# sensors.net
KiCad netlist of a schematic drawn in Altium Designer
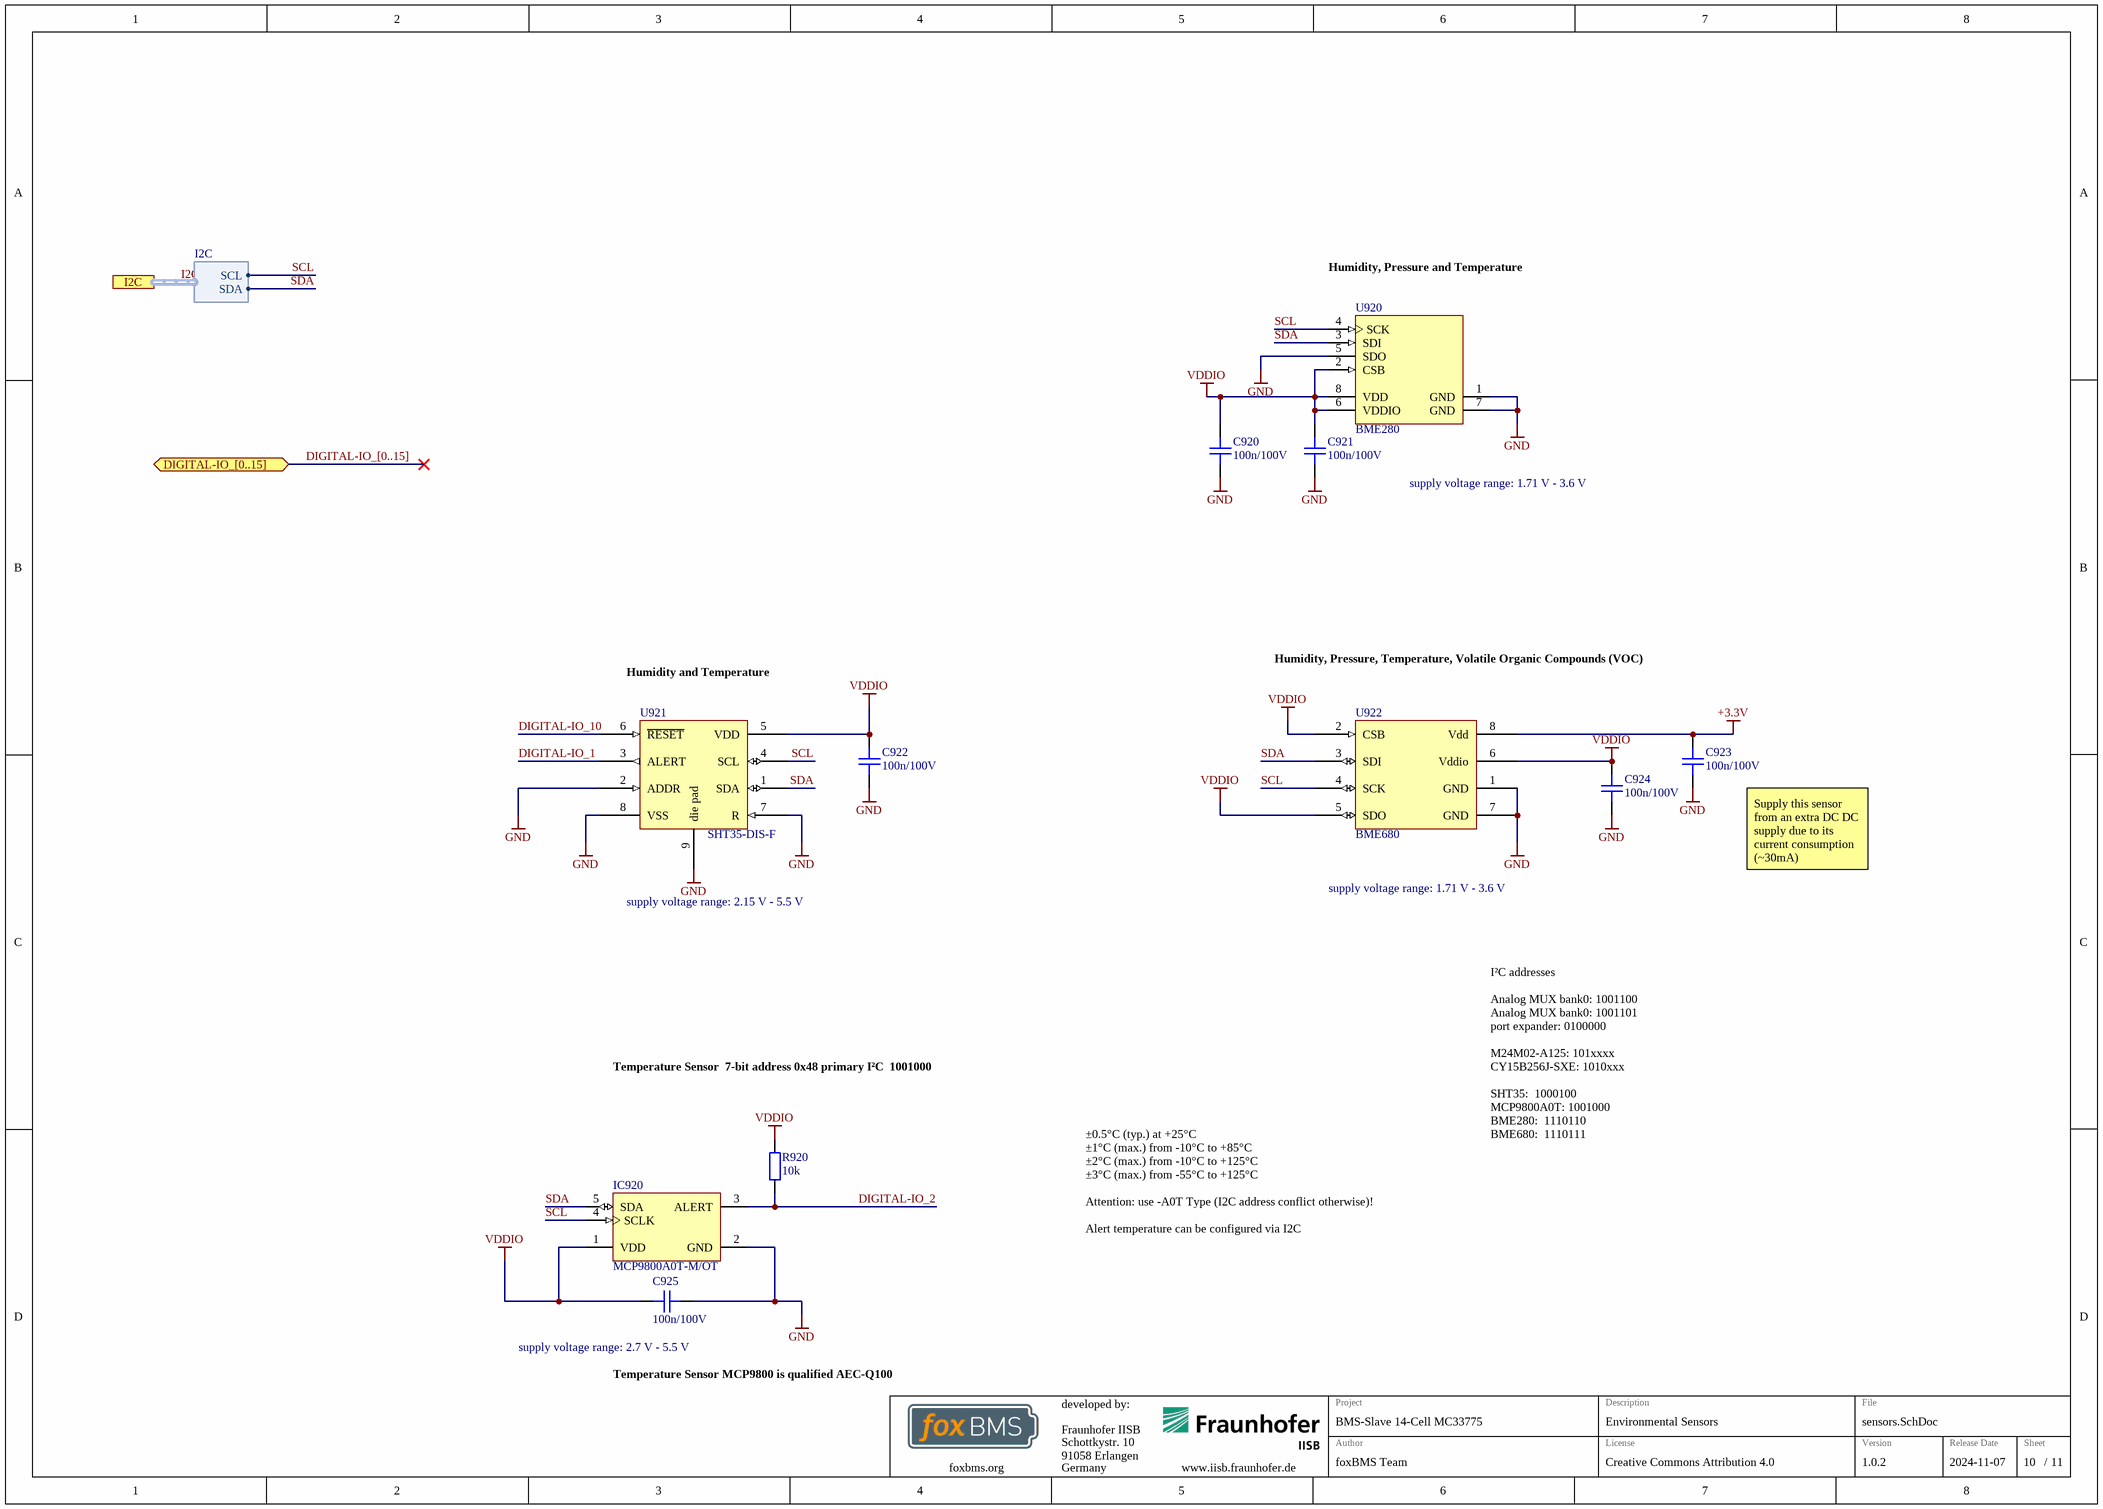
[diagram p0: sensors.SchDoc]

(export (version "E")
  (design (tool "Eeschema 10.0.6"))
  (components
    (comp (ref "C920")
      (value "100n/100V")
      (footprint "CAPC1608X08N")
      (description "MLCC")
      (fields (field (name "PART NUMBER") "gen_C_ceramic_100n_100V_X7R_0603"))
      (libsource (lib "OE750") (part "C"))
    )
    (comp (ref "C921")
      (value "100n/100V")
      (footprint "CAPC1608X08N")
      (description "MLCC")
      (fields (field (name "PART NUMBER") "gen_C_ceramic_100n_100V_X7R_0603"))
      (libsource (lib "OE750") (part "C"))
    )
    (comp (ref "C922")
      (value "100n/100V")
      (footprint "CAPC1608X08N")
      (description "MLCC")
      (fields (field (name "PART NUMBER") "gen_C_ceramic_100n_100V_X7R_0603"))
      (libsource (lib "OE750") (part "C"))
    )
    (comp (ref "C923")
      (value "100n/100V")
      (footprint "CAPC1608X08N")
      (description "MLCC")
      (fields (field (name "PART NUMBER") "gen_C_ceramic_100n_100V_X7R_0603"))
      (libsource (lib "OE750") (part "C"))
    )
    (comp (ref "C924")
      (value "100n/100V")
      (footprint "CAPC1608X08N")
      (description "MLCC")
      (fields (field (name "PART NUMBER") "gen_C_ceramic_100n_100V_X7R_0603"))
      (libsource (lib "OE750") (part "C"))
    )
    (comp (ref "C925")
      (value "100n/100V")
      (footprint "CAPC1608X08N")
      (description "MLCC")
      (fields (field (name "PART NUMBER") "gen_C_ceramic_100n_100V_X7R_0603"))
      (libsource (lib "OE750") (part "C"))
    )
    (comp (ref "IC920")
      (value "MCP9800A0T-M/OT")
      (footprint "SOT-23-OT5_L")
      (libsource (lib "Altium Content Vault") (part "SEN-TEMP-MCP980X-5"))
    )
    (comp (ref "R920")
      (value "10k")
      (footprint "RESC1608X05N")
      (description "SMD Resistor 10k 0603")
      (fields (field (name "PART NUMBER") "gen_R_10k_0603") (field (name "TOLERANCE") "1%"))
      (libsource (lib "OE750") (part "R"))
    )
    (comp (ref "U920")
      (value "BME280")
      (footprint "BOSC-BME280-8_V")
      (description "Low power pressure, temperature & humidity sensor")
      (fields (field (name "MANUFACTURER") "Bosch Sensortec"))
      (libsource (lib "OE750") (part "BME280"))
    )
    (comp (ref "U921")
      (value "SHT35-DIS-F")
      (footprint "SHT3X")
      (description "Humidity/Temp Sensor, Digital, Dfn-8")
      (fields (field (name "MANUFACTURER") "Sensirion"))
      (libsource (lib "OE750") (part "SHT3x-DIS"))
    )
    (comp (ref "U922")
      (value "BME680")
      (footprint "BME680")
      (description "Low power gas, pressure, temperature & humidity sensor")
      (fields (field (name "MANUFACTURER") "Bosch Sensortec"))
      (libsource (lib "OE750") (part "BME680"))
    )
  )
  (nets
    (net (code "15") (name "+3.3V") (class "Default")
      (node (ref "C923") (pin "2") (pinfunction "2_2") (pintype "passive"))
      (node (ref "U922") (pin "8") (pinfunction "Vdd_8") (pintype "power_in"))
    )
    (net (code "16") (name "/DIGITAL-IO_1") (class "Default")
      (node (ref "U921") (pin "3") (pinfunction "ALERT_3") (pintype "output"))
    )
    (net (code "17") (name "/DIGITAL-IO_2") (class "Default")
      (node (ref "IC920") (pin "3") (pinfunction "ALERT_3") (pintype "open_collector"))
      (node (ref "R920") (pin "1") (pinfunction "1_1") (pintype "passive"))
    )
    (net (code "18") (name "/DIGITAL-IO_10") (class "Default")
      (node (ref "U921") (pin "6") (pinfunction "~{RESET}_6") (pintype "input"))
    )
    (net (code "21") (name "/SCL") (class "Default")
      (node (ref "IC920") (pin "4") (pinfunction "SCLK_4") (pintype "input"))
      (node (ref "U920") (pin "4") (pinfunction "SCK_4") (pintype "input"))
      (node (ref "U921") (pin "4") (pinfunction "SCL_4") (pintype "bidirectional"))
      (node (ref "U922") (pin "4") (pinfunction "SCK_4") (pintype "bidirectional"))
    )
    (net (code "22") (name "/SDA") (class "Default")
      (node (ref "IC920") (pin "5") (pinfunction "SDA_5") (pintype "bidirectional"))
      (node (ref "U920") (pin "3") (pinfunction "SDI_3") (pintype "input"))
      (node (ref "U921") (pin "1") (pinfunction "SDA_1") (pintype "bidirectional"))
      (node (ref "U922") (pin "3") (pinfunction "SDI_3") (pintype "bidirectional"))
    )
    (net (code "23") (name "GND") (class "Default")
      (node (ref "C920") (pin "1") (pinfunction "1_1") (pintype "passive"))
      (node (ref "C921") (pin "1") (pinfunction "1_1") (pintype "passive"))
      (node (ref "C922") (pin "1") (pinfunction "1_1") (pintype "passive"))
      (node (ref "C923") (pin "1") (pinfunction "1_1") (pintype "passive"))
      (node (ref "C924") (pin "1") (pinfunction "1_1") (pintype "passive"))
      (node (ref "C925") (pin "1") (pinfunction "1_1") (pintype "passive"))
      (node (ref "IC920") (pin "2") (pinfunction "GND_2") (pintype "power_in"))
      (node (ref "U920") (pin "1") (pinfunction "GND_1") (pintype "power_in"))
      (node (ref "U920") (pin "5") (pinfunction "SDO_5") (pintype "passive"))
      (node (ref "U920") (pin "7") (pinfunction "GND_7") (pintype "power_in"))
      (node (ref "U921") (pin "2") (pinfunction "ADDR_2") (pintype "input"))
      (node (ref "U921") (pin "7") (pinfunction "R_7") (pintype "input"))
      (node (ref "U921") (pin "8") (pinfunction "VSS_8") (pintype "power_in"))
      (node (ref "U921") (pin "9") (pinfunction "die_pad_9") (pintype "power_in"))
      (node (ref "U922") (pin "1") (pinfunction "GND_1") (pintype "power_in"))
      (node (ref "U922") (pin "7") (pinfunction "GND_7") (pintype "power_in"))
    )
    (net (code "24") (name "VDDIO") (class "Default")
      (node (ref "C920") (pin "2") (pinfunction "2_2") (pintype "passive"))
      (node (ref "C921") (pin "2") (pinfunction "2_2") (pintype "passive"))
      (node (ref "C922") (pin "2") (pinfunction "2_2") (pintype "passive"))
      (node (ref "C924") (pin "2") (pinfunction "2_2") (pintype "passive"))
      (node (ref "C925") (pin "2") (pinfunction "2_2") (pintype "passive"))
      (node (ref "IC920") (pin "1") (pinfunction "VDD_1") (pintype "power_in"))
      (node (ref "R920") (pin "2") (pinfunction "2_2") (pintype "passive"))
      (node (ref "U920") (pin "2") (pinfunction "CSB_2") (pintype "input"))
      (node (ref "U920") (pin "6") (pinfunction "VDDIO_6") (pintype "power_in"))
      (node (ref "U920") (pin "8") (pinfunction "VDD_8") (pintype "power_in"))
      (node (ref "U921") (pin "5") (pinfunction "VDD_5") (pintype "power_in"))
      (node (ref "U922") (pin "2") (pinfunction "CSB_2") (pintype "input"))
      (node (ref "U922") (pin "5") (pinfunction "SDO_5") (pintype "bidirectional"))
      (node (ref "U922") (pin "6") (pinfunction "Vddio_6") (pintype "power_in"))
    )
  )
)
